# Modul_PCB.net
KiCad netlist of a schematic drawn in EAGLE
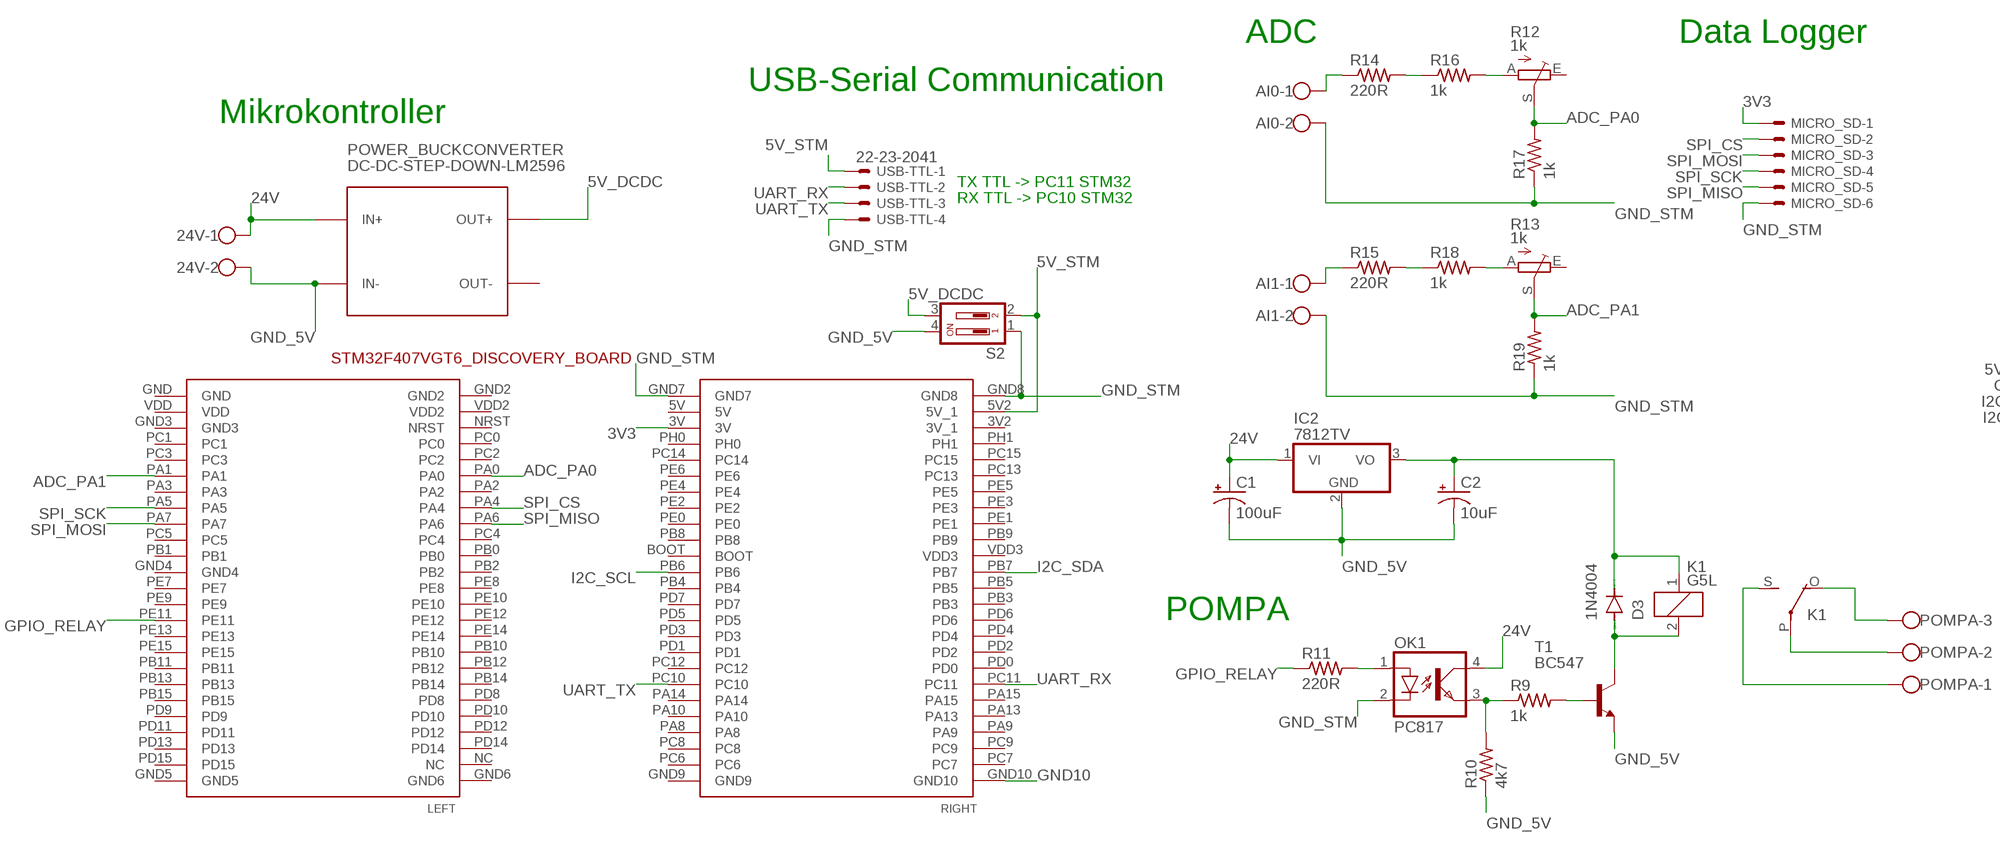
[diagram p0: schematic, sheet 1, part 1 of 2]
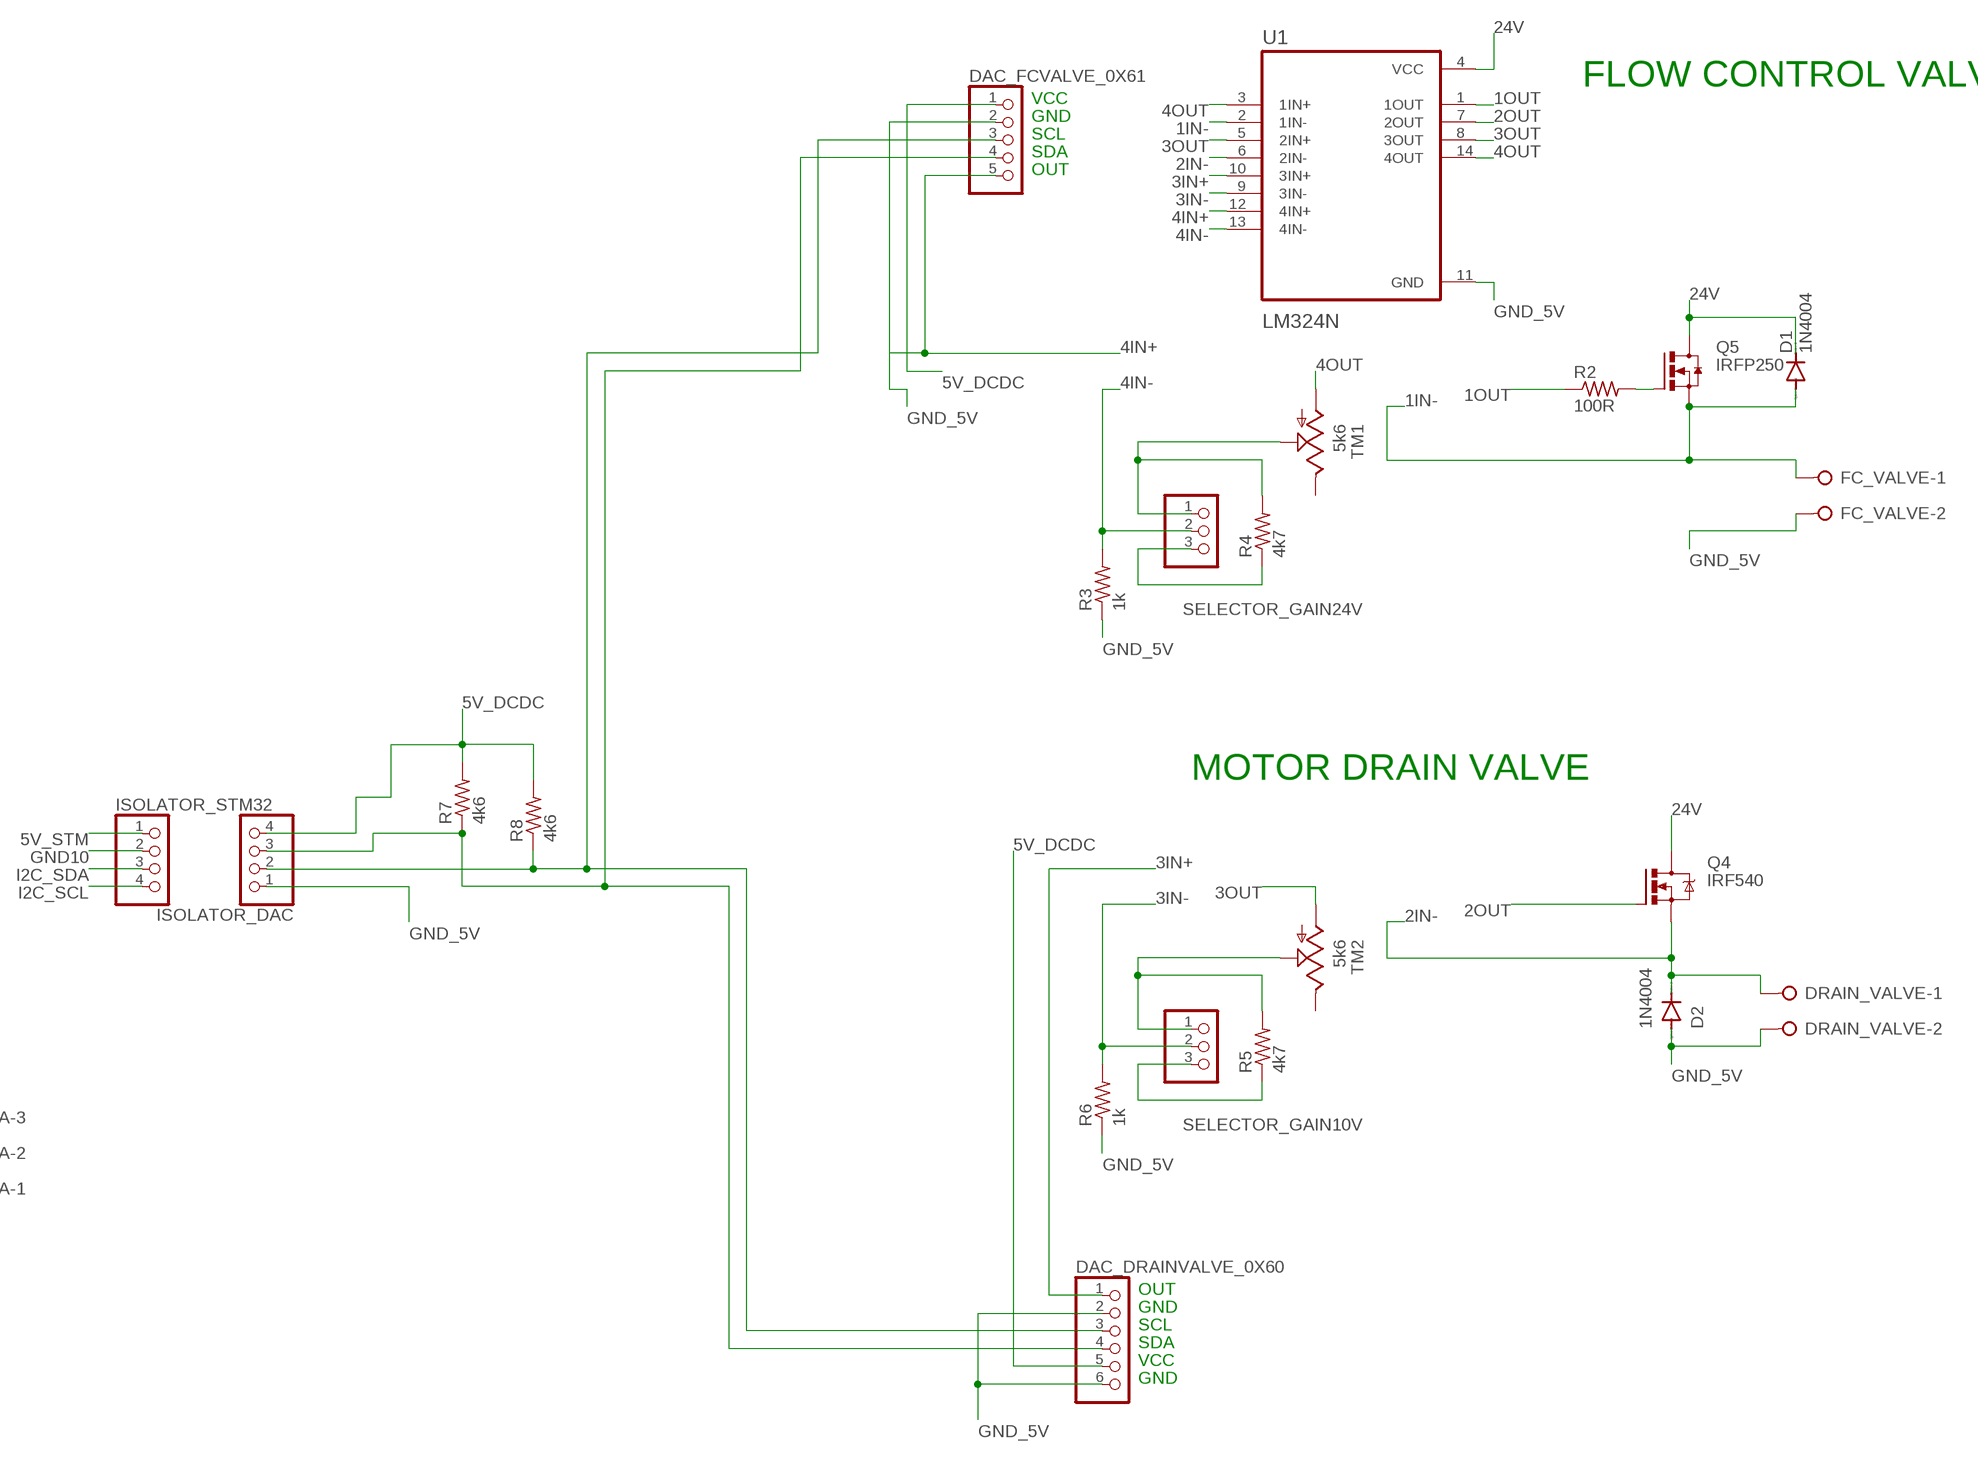
[diagram p1: schematic, sheet 1, part 2 of 2]

(export (version "E")
  (design (tool "Eeschema 10.0.6"))
  (components
    (comp (ref "24V")
      (value "W237-102")
      (footprint "eagle-import:W237-102")
      (fields (field (name "MPN") "237-102"))
      (libsource (lib "eagle-import") (part "W237-102"))
    )
    (comp (ref "AI0")
      (value "W237-102")
      (footprint "eagle-import:W237-102")
      (fields (field (name "MPN") "237-102"))
      (libsource (lib "eagle-import") (part "W237-102"))
    )
    (comp (ref "AI1")
      (value "W237-102")
      (footprint "eagle-import:W237-102")
      (fields (field (name "MPN") "237-102"))
      (libsource (lib "eagle-import") (part "W237-102"))
    )
    (comp (ref "C1")
      (value "100uF")
      (footprint "eagle-import:E2,5-6")
      (libsource (lib "eagle-import") (part "CPOL-USE2.5-6"))
    )
    (comp (ref "C2")
      (value "10uF")
      (footprint "eagle-import:E2,5-6")
      (libsource (lib "eagle-import") (part "CPOL-USE2.5-6"))
    )
    (comp (ref "D1")
      (value "1N4004")
      (footprint "eagle-import:DO41-10")
      (libsource (lib "eagle-import") (part "1N4004"))
    )
    (comp (ref "D2")
      (value "1N4004")
      (footprint "eagle-import:DO41-10")
      (libsource (lib "eagle-import") (part "1N4004"))
    )
    (comp (ref "D3")
      (value "1N4004")
      (footprint "eagle-import:DO41-10")
      (libsource (lib "eagle-import") (part "1N4004"))
    )
    (comp (ref "DAC_DRAINVALVE_0X60")
      (value "PINHD-1X6")
      (footprint "eagle-import:1X06")
      (libsource (lib "eagle-import") (part "PINHD-1X6"))
    )
    (comp (ref "DAC_FCVALVE_0X61")
      (value "PINHD-1X5")
      (footprint "eagle-import:1X05")
      (libsource (lib "eagle-import") (part "PINHD-1X5"))
    )
    (comp (ref "DRAIN_VALVE")
      (value "W237-02P")
      (footprint "eagle-import:W237-132")
      (libsource (lib "eagle-import") (part "W237-02P"))
    )
    (comp (ref "FC_VALVE")
      (value "W237-02P")
      (footprint "eagle-import:W237-132")
      (libsource (lib "eagle-import") (part "W237-02P"))
    )
    (comp (ref "IC2")
      (value "7812TV")
      (footprint "eagle-import:TO220V")
      (libsource (lib "eagle-import") (part "78TV12"))
    )
    (comp (ref "ISOLATOR_DAC")
      (value "PINHD-1X4")
      (footprint "eagle-import:1X04")
      (libsource (lib "eagle-import") (part "PINHD-1X4"))
    )
    (comp (ref "ISOLATOR_STM32")
      (value "PINHD-1X4")
      (footprint "eagle-import:1X04")
      (libsource (lib "eagle-import") (part "PINHD-1X4"))
    )
    (comp (ref "K1")
      (value "G5L")
      (footprint "eagle-import:G5LE")
      (libsource (lib "eagle-import") (part "G5L"))
    )
    (comp (ref "MICRO_SD")
      (value "22-23-2061")
      (footprint "eagle-import:22-23-2061")
      (fields (field (name "MF") "MOLEX"))
      (libsource (lib "eagle-import") (part "22-23-2061"))
    )
    (comp (ref "OK1")
      (value "PC817")
      (footprint "eagle-import:DIL04")
      (fields (field (name "MPN") "PC817X4J000F"))
      (libsource (lib "eagle-import") (part "PC817"))
    )
    (comp (ref "POMPA")
      (value "W237-103")
      (footprint "eagle-import:W237-103")
      (fields (field (name "MPN") "237-103"))
      (libsource (lib "eagle-import") (part "W237-103"))
    )
    (comp (ref "POWER_BUCKCONVERTER")
      (value "DC-DC-STEP-DOWN-LM2596")
      (footprint "eagle-import:DC-DC-STEP-DOWN-LM2596")
      (libsource (lib "eagle-import") (part "DC-DC-STEP-DOWN-LM2596"))
    )
    (comp (ref "Q4")
      (value "IRF540")
      (footprint "eagle-import:TO220BV")
      (libsource (lib "eagle-import") (part "IRF540"))
    )
    (comp (ref "Q5")
      (value "IRFP250")
      (footprint "eagle-import:TO-247AD-V")
      (libsource (lib "eagle-import") (part "IRFP250"))
    )
    (comp (ref "R2")
      (value "100R")
      (footprint "eagle-import:0207_10")
      (libsource (lib "eagle-import") (part "R-US_0207/10"))
    )
    (comp (ref "R3")
      (value "1k")
      (footprint "eagle-import:0207_10")
      (libsource (lib "eagle-import") (part "R-US_0207/10"))
    )
    (comp (ref "R4")
      (value "4k7")
      (footprint "eagle-import:0207_10")
      (libsource (lib "eagle-import") (part "R-US_0207/10"))
    )
    (comp (ref "R5")
      (value "4k7")
      (footprint "eagle-import:0207_10")
      (libsource (lib "eagle-import") (part "R-US_0207/10"))
    )
    (comp (ref "R6")
      (value "1k")
      (footprint "eagle-import:0207_10")
      (libsource (lib "eagle-import") (part "R-US_0207/10"))
    )
    (comp (ref "R7")
      (value "4k6")
      (footprint "eagle-import:0207_10")
      (libsource (lib "eagle-import") (part "R-US_0207/10"))
    )
    (comp (ref "R8")
      (value "4k6")
      (footprint "eagle-import:0207_10")
      (libsource (lib "eagle-import") (part "R-US_0207/10"))
    )
    (comp (ref "R9")
      (value "1k")
      (footprint "eagle-import:0207_10")
      (libsource (lib "eagle-import") (part "R-US_0207/10"))
    )
    (comp (ref "R10")
      (value "4k7")
      (footprint "eagle-import:0207_10")
      (libsource (lib "eagle-import") (part "R-US_0207/10"))
    )
    (comp (ref "R11")
      (value "220R")
      (footprint "eagle-import:0207_10")
      (libsource (lib "eagle-import") (part "R-US_0207/10"))
    )
    (comp (ref "R12")
      (value "1k")
      (footprint "eagle-import:RJ9W")
      (libsource (lib "eagle-import") (part "TRIM_EU-RJ9W"))
    )
    (comp (ref "R13")
      (value "1k")
      (footprint "eagle-import:RJ9W")
      (libsource (lib "eagle-import") (part "TRIM_EU-RJ9W"))
    )
    (comp (ref "R14")
      (value "220R")
      (footprint "eagle-import:0207_10")
      (libsource (lib "eagle-import") (part "R-US_0207/10"))
    )
    (comp (ref "R15")
      (value "220R")
      (footprint "eagle-import:0207_10")
      (libsource (lib "eagle-import") (part "R-US_0207/10"))
    )
    (comp (ref "R16")
      (value "1k")
      (footprint "eagle-import:0207_10")
      (libsource (lib "eagle-import") (part "R-US_0207/10"))
    )
    (comp (ref "R17")
      (value "1k")
      (footprint "eagle-import:0207_10")
      (libsource (lib "eagle-import") (part "R-US_0207/10"))
    )
    (comp (ref "R18")
      (value "1k")
      (footprint "eagle-import:0207_10")
      (libsource (lib "eagle-import") (part "R-US_0207/10"))
    )
    (comp (ref "R19")
      (value "1k")
      (footprint "eagle-import:0207_10")
      (libsource (lib "eagle-import") (part "R-US_0207/10"))
    )
    (comp (ref "S2")
      (value "DS02")
      (footprint "eagle-import:DS-02")
      (libsource (lib "eagle-import") (part "DS02"))
    )
    (comp (ref "SELECTOR_GAIN10V")
      (value "PINHD-1X3")
      (footprint "eagle-import:1X03")
      (libsource (lib "eagle-import") (part "PINHD-1X3"))
    )
    (comp (ref "SELECTOR_GAIN24V")
      (value "PINHD-1X3")
      (footprint "eagle-import:1X03")
      (libsource (lib "eagle-import") (part "PINHD-1X3"))
    )
    (comp (ref "STM32F407VGT6_DISCOVERY_BOARD")
      (value "STM32F4-DISCOVERY")
      (footprint "eagle-import:STM32F407VG")
      (libsource (lib "eagle-import") (part "STM32F4-DISCOVERY"))
    )
    (comp (ref "T1")
      (value "BC547")
      (footprint "eagle-import:TO92")
      (libsource (lib "eagle-import") (part "BC547"))
    )
    (comp (ref "TM1")
      (value "5k6")
      (footprint "eagle-import:6MM")
      (libsource (lib "eagle-import") (part "TRIM"))
    )
    (comp (ref "TM2")
      (value "5k6")
      (footprint "eagle-import:6MM")
      (libsource (lib "eagle-import") (part "TRIM"))
    )
    (comp (ref "U1")
      (value "LM324N")
      (footprint "eagle-import:DIP794W45P254L1969H508Q14")
      (fields (field (name "MF") "STMicroelectronics"))
      (libsource (lib "eagle-import") (part "LM324N"))
    )
    (comp (ref "USB-TTL")
      (value "22-23-2041")
      (footprint "eagle-import:22-23-2041")
      (fields (field (name "MF") "MOLEX"))
      (libsource (lib "eagle-import") (part "22-23-2041"))
    )
  )
  (nets
    (net (code "1") (name "/1IN-") (class "Default")
      (node (ref "D1") (pin "A") (pinfunction "A_A") (pintype "passive"))
      (node (ref "FC_VALVE") (pin "1") (pinfunction "KL_1") (pintype "passive"))
      (node (ref "Q5") (pin "S") (pinfunction "S_S") (pintype "passive"))
      (node (ref "U1") (pin "2") (pinfunction "1IN-_2") (pintype "input"))
    )
    (net (code "2") (name "/1OUT") (class "Default")
      (node (ref "R2") (pin "1") (pinfunction "1_1") (pintype "passive"))
      (node (ref "U1") (pin "1") (pinfunction "1OUT_1") (pintype "output"))
    )
    (net (code "3") (name "/2IN-") (class "Default")
      (node (ref "D2") (pin "C") (pinfunction "C_C") (pintype "passive"))
      (node (ref "DRAIN_VALVE") (pin "1") (pinfunction "KL_1") (pintype "passive"))
      (node (ref "Q4") (pin "S") (pinfunction "S_S") (pintype "passive"))
      (node (ref "U1") (pin "6") (pinfunction "2IN-_6") (pintype "input"))
    )
    (net (code "4") (name "/2OUT") (class "Default")
      (node (ref "Q4") (pin "G") (pinfunction "G_G") (pintype "passive"))
      (node (ref "U1") (pin "7") (pinfunction "2OUT_7") (pintype "output"))
    )
    (net (code "5") (name "/3IN+") (class "Default")
      (node (ref "DAC_DRAINVALVE_0X60") (pin "1") (pinfunction "1_1") (pintype "passive"))
      (node (ref "U1") (pin "10") (pinfunction "3IN+_10") (pintype "input"))
    )
    (net (code "6") (name "/3IN-") (class "Default")
      (node (ref "R6") (pin "2") (pinfunction "2_2") (pintype "passive"))
      (node (ref "SELECTOR_GAIN10V") (pin "2") (pinfunction "2_2") (pintype "passive"))
      (node (ref "U1") (pin "9") (pinfunction "3IN-_9") (pintype "input"))
    )
    (net (code "7") (name "/3OUT") (class "Default")
      (node (ref "TM2") (pin "A") (pinfunction "A_A") (pintype "passive"))
      (node (ref "U1") (pin "5") (pinfunction "2IN+_5") (pintype "input"))
      (node (ref "U1") (pin "8") (pinfunction "3OUT_8") (pintype "output"))
    )
    (net (code "8") (name "/3V3") (class "Default")
      (node (ref "MICRO_SD") (pin "1") (pinfunction "S_1") (pintype "passive"))
      (node (ref "STM32F407VGT6_DISCOVERY_BOARD") (pin "3V") (pinfunction "3V_3V") (pintype "bidirectional"))
    )
    (net (code "9") (name "/4IN+") (class "Default")
      (node (ref "DAC_FCVALVE_0X61") (pin "5") (pinfunction "5_5") (pintype "passive"))
      (node (ref "U1") (pin "12") (pinfunction "4IN+_12") (pintype "input"))
    )
    (net (code "10") (name "/4IN-") (class "Default")
      (node (ref "R3") (pin "2") (pinfunction "2_2") (pintype "passive"))
      (node (ref "SELECTOR_GAIN24V") (pin "2") (pinfunction "2_2") (pintype "passive"))
      (node (ref "U1") (pin "13") (pinfunction "4IN-_13") (pintype "input"))
    )
    (net (code "11") (name "/4OUT") (class "Default")
      (node (ref "TM1") (pin "A") (pinfunction "A_A") (pintype "passive"))
      (node (ref "U1") (pin "14") (pinfunction "4OUT_14") (pintype "output"))
      (node (ref "U1") (pin "3") (pinfunction "1IN+_3") (pintype "input"))
    )
    (net (code "12") (name "/5V_DCDC") (class "Default")
      (node (ref "DAC_DRAINVALVE_0X60") (pin "5") (pinfunction "5_5") (pintype "passive"))
      (node (ref "DAC_FCVALVE_0X61") (pin "1") (pinfunction "1_1") (pintype "passive"))
      (node (ref "ISOLATOR_DAC") (pin "4") (pinfunction "4_4") (pintype "passive"))
      (node (ref "POWER_BUCKCONVERTER") (pin "OUT+") (pinfunction "OUT+_OUT+") (pintype "bidirectional"))
      (node (ref "R7") (pin "2") (pinfunction "2_2") (pintype "passive"))
      (node (ref "R8") (pin "2") (pinfunction "2_2") (pintype "passive"))
      (node (ref "S2") (pin "3") (pinfunction "3_3") (pintype "passive"))
    )
    (net (code "13") (name "/5V_STM") (class "Default")
      (node (ref "ISOLATOR_STM32") (pin "1") (pinfunction "1_1") (pintype "passive"))
      (node (ref "S2") (pin "2") (pinfunction "2_2") (pintype "passive"))
      (node (ref "STM32F407VGT6_DISCOVERY_BOARD") (pin "5V2") (pinfunction "5V_1_5V2") (pintype "bidirectional"))
      (node (ref "USB-TTL") (pin "1") (pinfunction "S_1") (pintype "passive"))
    )
    (net (code "14") (name "/24V") (class "Default")
      (node (ref "24V") (pin "1") (pinfunction "KL_1") (pintype "passive"))
      (node (ref "C1") (pin "+") (pinfunction "+_+") (pintype "passive"))
      (node (ref "D1") (pin "C") (pinfunction "C_C") (pintype "passive"))
      (node (ref "IC2") (pin "1") (pinfunction "VI_1") (pintype "input"))
      (node (ref "OK1") (pin "4") (pinfunction "COL_4") (pintype "passive"))
      (node (ref "POWER_BUCKCONVERTER") (pin "IN+") (pinfunction "IN+_IN+") (pintype "bidirectional"))
      (node (ref "Q4") (pin "D") (pinfunction "D_D") (pintype "passive"))
      (node (ref "Q5") (pin "D") (pinfunction "D_D") (pintype "passive"))
      (node (ref "U1") (pin "4") (pinfunction "VCC_4") (pintype "power_in"))
    )
    (net (code "15") (name "/ADC_PA0") (class "Default")
      (node (ref "R12") (pin "S") (pinfunction "S_S") (pintype "passive"))
      (node (ref "R17") (pin "2") (pinfunction "2_2") (pintype "passive"))
      (node (ref "STM32F407VGT6_DISCOVERY_BOARD") (pin "PA0") (pinfunction "PA0_PA0") (pintype "bidirectional"))
    )
    (net (code "16") (name "/ADC_PA1") (class "Default")
      (node (ref "R13") (pin "S") (pinfunction "S_S") (pintype "passive"))
      (node (ref "R19") (pin "2") (pinfunction "2_2") (pintype "passive"))
      (node (ref "STM32F407VGT6_DISCOVERY_BOARD") (pin "PA1") (pinfunction "PA1_PA1") (pintype "bidirectional"))
    )
    (net (code "17") (name "/GND10") (class "Default")
      (node (ref "ISOLATOR_STM32") (pin "2") (pinfunction "2_2") (pintype "passive"))
      (node (ref "STM32F407VGT6_DISCOVERY_BOARD") (pin "GND10") (pinfunction "GND10_GND10") (pintype "bidirectional"))
    )
    (net (code "18") (name "/GND_5V") (class "Default")
      (node (ref "24V") (pin "2") (pinfunction "KL_2") (pintype "passive"))
      (node (ref "C1") (pin "-") (pinfunction "-_-") (pintype "passive"))
      (node (ref "C2") (pin "-") (pinfunction "-_-") (pintype "passive"))
      (node (ref "D2") (pin "A") (pinfunction "A_A") (pintype "passive"))
      (node (ref "DAC_DRAINVALVE_0X60") (pin "2") (pinfunction "2_2") (pintype "passive"))
      (node (ref "DAC_DRAINVALVE_0X60") (pin "6") (pinfunction "6_6") (pintype "passive"))
      (node (ref "DAC_FCVALVE_0X61") (pin "2") (pinfunction "2_2") (pintype "passive"))
      (node (ref "DRAIN_VALVE") (pin "2") (pinfunction "KL_2") (pintype "passive"))
      (node (ref "FC_VALVE") (pin "2") (pinfunction "KL_2") (pintype "passive"))
      (node (ref "IC2") (pin "2") (pinfunction "GND_2") (pintype "passive"))
      (node (ref "ISOLATOR_DAC") (pin "1") (pinfunction "1_1") (pintype "passive"))
      (node (ref "POWER_BUCKCONVERTER") (pin "IN-") (pinfunction "IN-_IN-") (pintype "bidirectional"))
      (node (ref "R10") (pin "1") (pinfunction "1_1") (pintype "passive"))
      (node (ref "R3") (pin "1") (pinfunction "1_1") (pintype "passive"))
      (node (ref "R6") (pin "1") (pinfunction "1_1") (pintype "passive"))
      (node (ref "S2") (pin "4") (pinfunction "4_4") (pintype "passive"))
      (node (ref "T1") (pin "1") (pinfunction "E_1") (pintype "passive"))
      (node (ref "U1") (pin "11") (pinfunction "GND_11") (pintype "power_in"))
    )
    (net (code "19") (name "/GND_STM") (class "Default")
      (node (ref "AI0") (pin "2") (pinfunction "KL_2") (pintype "passive"))
      (node (ref "AI1") (pin "2") (pinfunction "KL_2") (pintype "passive"))
      (node (ref "MICRO_SD") (pin "6") (pinfunction "S_6") (pintype "passive"))
      (node (ref "OK1") (pin "2") (pinfunction "C_2") (pintype "passive"))
      (node (ref "R17") (pin "1") (pinfunction "1_1") (pintype "passive"))
      (node (ref "R19") (pin "1") (pinfunction "1_1") (pintype "passive"))
      (node (ref "S2") (pin "1") (pinfunction "1_1") (pintype "passive"))
      (node (ref "STM32F407VGT6_DISCOVERY_BOARD") (pin "GND7") (pinfunction "GND7_GND7") (pintype "bidirectional"))
      (node (ref "STM32F407VGT6_DISCOVERY_BOARD") (pin "GND8") (pinfunction "GND8_GND8") (pintype "bidirectional"))
      (node (ref "USB-TTL") (pin "4") (pinfunction "S_4") (pintype "passive"))
    )
    (net (code "20") (name "/GPIO_RELAY") (class "Default")
      (node (ref "R11") (pin "1") (pinfunction "1_1") (pintype "passive"))
      (node (ref "STM32F407VGT6_DISCOVERY_BOARD") (pin "PE11") (pinfunction "PE11_PE11") (pintype "bidirectional"))
    )
    (net (code "21") (name "/I2C_SCL") (class "Default")
      (node (ref "ISOLATOR_STM32") (pin "4") (pinfunction "4_4") (pintype "passive"))
      (node (ref "STM32F407VGT6_DISCOVERY_BOARD") (pin "PB6") (pinfunction "PB6_PB6") (pintype "bidirectional"))
    )
    (net (code "22") (name "/I2C_SDA") (class "Default")
      (node (ref "ISOLATOR_STM32") (pin "3") (pinfunction "3_3") (pintype "passive"))
      (node (ref "STM32F407VGT6_DISCOVERY_BOARD") (pin "PB7") (pinfunction "PB7_PB7") (pintype "bidirectional"))
    )
    (net (code "23") (name "/SPI_CS") (class "Default")
      (node (ref "MICRO_SD") (pin "2") (pinfunction "S_2") (pintype "passive"))
      (node (ref "STM32F407VGT6_DISCOVERY_BOARD") (pin "PA4") (pinfunction "PA4_PA4") (pintype "bidirectional"))
    )
    (net (code "24") (name "/SPI_MISO") (class "Default")
      (node (ref "MICRO_SD") (pin "5") (pinfunction "S_5") (pintype "passive"))
      (node (ref "STM32F407VGT6_DISCOVERY_BOARD") (pin "PA6") (pinfunction "PA6_PA6") (pintype "bidirectional"))
    )
    (net (code "25") (name "/SPI_MOSI") (class "Default")
      (node (ref "MICRO_SD") (pin "3") (pinfunction "S_3") (pintype "passive"))
      (node (ref "STM32F407VGT6_DISCOVERY_BOARD") (pin "PA7") (pinfunction "PA7_PA7") (pintype "bidirectional"))
    )
    (net (code "26") (name "/SPI_SCK") (class "Default")
      (node (ref "MICRO_SD") (pin "4") (pinfunction "S_4") (pintype "passive"))
      (node (ref "STM32F407VGT6_DISCOVERY_BOARD") (pin "PA5") (pinfunction "PA5_PA5") (pintype "bidirectional"))
    )
    (net (code "27") (name "/UART_RX") (class "Default")
      (node (ref "STM32F407VGT6_DISCOVERY_BOARD") (pin "PC11") (pinfunction "PC11_PC11") (pintype "bidirectional"))
      (node (ref "USB-TTL") (pin "2") (pinfunction "S_2") (pintype "passive"))
    )
    (net (code "28") (name "/UART_TX") (class "Default")
      (node (ref "STM32F407VGT6_DISCOVERY_BOARD") (pin "PC10") (pinfunction "PC10_PC10") (pintype "bidirectional"))
      (node (ref "USB-TTL") (pin "3") (pinfunction "S_3") (pintype "passive"))
    )
    (net (code "29") (name "Net-(AI0A-KL)") (class "Default")
      (node (ref "AI0") (pin "1") (pinfunction "KL_1") (pintype "passive"))
      (node (ref "R14") (pin "1") (pinfunction "1_1") (pintype "passive"))
    )
    (net (code "30") (name "Net-(AI1A-KL)") (class "Default")
      (node (ref "AI1") (pin "1") (pinfunction "KL_1") (pintype "passive"))
      (node (ref "R15") (pin "1") (pinfunction "1_1") (pintype "passive"))
    )
    (net (code "31") (name "Net-(DAC_DRAINVALVE_0X60-Pad3)") (class "Default")
      (node (ref "DAC_DRAINVALVE_0X60") (pin "3") (pinfunction "3_3") (pintype "passive"))
      (node (ref "DAC_FCVALVE_0X61") (pin "3") (pinfunction "3_3") (pintype "passive"))
      (node (ref "ISOLATOR_DAC") (pin "2") (pinfunction "2_2") (pintype "passive"))
      (node (ref "R8") (pin "1") (pinfunction "1_1") (pintype "passive"))
    )
    (net (code "32") (name "Net-(DAC_DRAINVALVE_0X60-Pad4)") (class "Default")
      (node (ref "DAC_DRAINVALVE_0X60") (pin "4") (pinfunction "4_4") (pintype "passive"))
      (node (ref "DAC_FCVALVE_0X61") (pin "4") (pinfunction "4_4") (pintype "passive"))
      (node (ref "ISOLATOR_DAC") (pin "3") (pinfunction "3_3") (pintype "passive"))
      (node (ref "R7") (pin "1") (pinfunction "1_1") (pintype "passive"))
    )
    (net (code "33") (name "Net-(IC2-VO)") (class "Default")
      (node (ref "C2") (pin "+") (pinfunction "+_+") (pintype "passive"))
      (node (ref "D3") (pin "C") (pinfunction "C_C") (pintype "passive"))
      (node (ref "IC2") (pin "3") (pinfunction "VO_3") (pintype "passive"))
      (node (ref "K1") (pin "1") (pinfunction "1_1") (pintype "passive"))
    )
    (net (code "34") (name "Net-(OK1-A)") (class "Default")
      (node (ref "OK1") (pin "1") (pinfunction "A_1") (pintype "passive"))
      (node (ref "R11") (pin "2") (pinfunction "2_2") (pintype "passive"))
    )
    (net (code "35") (name "Net-(OK1-EMIT)") (class "Default")
      (node (ref "OK1") (pin "3") (pinfunction "EMIT_3") (pintype "passive"))
      (node (ref "R10") (pin "2") (pinfunction "2_2") (pintype "passive"))
      (node (ref "R9") (pin "1") (pinfunction "1_1") (pintype "passive"))
    )
    (net (code "36") (name "Net-(POMPAA-KL)") (class "Default")
      (node (ref "K1") (pin "S") (pinfunction "S_S") (pintype "passive"))
      (node (ref "POMPA") (pin "1") (pinfunction "KL_1") (pintype "passive"))
    )
    (net (code "37") (name "Net-(POMPAB-KL)") (class "Default")
      (node (ref "K1") (pin "P") (pinfunction "P_P") (pintype "passive"))
      (node (ref "POMPA") (pin "2") (pinfunction "KL_2") (pintype "passive"))
    )
    (net (code "38") (name "Net-(POMPAC-KL)") (class "Default")
      (node (ref "K1") (pin "O") (pinfunction "O_O") (pintype "passive"))
      (node (ref "POMPA") (pin "3") (pinfunction "KL_3") (pintype "passive"))
    )
    (net (code "39") (name "Net-(Q5-PadG)") (class "Default")
      (node (ref "Q5") (pin "G") (pinfunction "G_G") (pintype "passive"))
      (node (ref "R2") (pin "2") (pinfunction "2_2") (pintype "passive"))
    )
    (net (code "40") (name "Net-(R4-Pad1)") (class "Default")
      (node (ref "R4") (pin "1") (pinfunction "1_1") (pintype "passive"))
      (node (ref "SELECTOR_GAIN24V") (pin "3") (pinfunction "3_3") (pintype "passive"))
    )
    (net (code "41") (name "Net-(R4-Pad2)") (class "Default")
      (node (ref "R4") (pin "2") (pinfunction "2_2") (pintype "passive"))
      (node (ref "SELECTOR_GAIN24V") (pin "1") (pinfunction "1_1") (pintype "passive"))
      (node (ref "TM1") (pin "S") (pinfunction "S_S") (pintype "passive"))
    )
    (net (code "42") (name "Net-(R5-Pad1)") (class "Default")
      (node (ref "R5") (pin "1") (pinfunction "1_1") (pintype "passive"))
      (node (ref "SELECTOR_GAIN10V") (pin "3") (pinfunction "3_3") (pintype "passive"))
    )
    (net (code "43") (name "Net-(R5-Pad2)") (class "Default")
      (node (ref "R5") (pin "2") (pinfunction "2_2") (pintype "passive"))
      (node (ref "SELECTOR_GAIN10V") (pin "1") (pinfunction "1_1") (pintype "passive"))
      (node (ref "TM2") (pin "S") (pinfunction "S_S") (pintype "passive"))
    )
    (net (code "44") (name "Net-(R12-PadA)") (class "Default")
      (node (ref "R12") (pin "A") (pinfunction "A_A") (pintype "passive"))
      (node (ref "R16") (pin "2") (pinfunction "2_2") (pintype "passive"))
    )
    (net (code "45") (name "Net-(R13-PadA)") (class "Default")
      (node (ref "R13") (pin "A") (pinfunction "A_A") (pintype "passive"))
      (node (ref "R18") (pin "2") (pinfunction "2_2") (pintype "passive"))
    )
    (net (code "46") (name "Net-(R14-Pad2)") (class "Default")
      (node (ref "R14") (pin "2") (pinfunction "2_2") (pintype "passive"))
      (node (ref "R16") (pin "1") (pinfunction "1_1") (pintype "passive"))
    )
    (net (code "47") (name "Net-(R15-Pad2)") (class "Default")
      (node (ref "R15") (pin "2") (pinfunction "2_2") (pintype "passive"))
      (node (ref "R18") (pin "1") (pinfunction "1_1") (pintype "passive"))
    )
    (net (code "48") (name "Net-(T1-B)") (class "Default")
      (node (ref "R9") (pin "2") (pinfunction "2_2") (pintype "passive"))
      (node (ref "T1") (pin "2") (pinfunction "B_2") (pintype "passive"))
    )
    (net (code "49") (name "Net-(T1-C)") (class "Default")
      (node (ref "D3") (pin "A") (pinfunction "A_A") (pintype "passive"))
      (node (ref "K1") (pin "2") (pinfunction "2_2") (pintype "passive"))
      (node (ref "T1") (pin "3") (pinfunction "C_3") (pintype "passive"))
    )
    (net (code "50") (name "unconnected-(POWER_BUCKCONVERTER-PadOUT-)") (class "Default")
      (node (ref "POWER_BUCKCONVERTER") (pin "OUT-") (pinfunction "OUT-_OUT-") (pintype "bidirectional"))
    )
    (net (code "51") (name "unconnected-(R12-PadE)") (class "Default")
      (node (ref "R12") (pin "E") (pinfunction "E_E") (pintype "passive"))
    )
    (net (code "52") (name "unconnected-(R13-PadE)") (class "Default")
      (node (ref "R13") (pin "E") (pinfunction "E_E") (pintype "passive"))
    )
    (net (code "53") (name "unconnected-(STM32F407VGT6_DISCOVERY_BOARD-3V_1-Pad3V2)") (class "Default")
      (node (ref "STM32F407VGT6_DISCOVERY_BOARD") (pin "3V2") (pinfunction "3V_1_3V2") (pintype "bidirectional"))
    )
    (net (code "54") (name "unconnected-(STM32F407VGT6_DISCOVERY_BOARD-Pad5V)") (class "Default")
      (node (ref "STM32F407VGT6_DISCOVERY_BOARD") (pin "5V") (pinfunction "5V_5V") (pintype "bidirectional"))
    )
    (net (code "55") (name "unconnected-(STM32F407VGT6_DISCOVERY_BOARD-PadBOOT)") (class "Default")
      (node (ref "STM32F407VGT6_DISCOVERY_BOARD") (pin "BOOT") (pinfunction "BOOT_BOOT") (pintype "bidirectional"))
    )
    (net (code "56") (name "unconnected-(STM32F407VGT6_DISCOVERY_BOARD-PadGND)") (class "Default")
      (node (ref "STM32F407VGT6_DISCOVERY_BOARD") (pin "GND") (pinfunction "GND_GND") (pintype "bidirectional"))
    )
    (net (code "57") (name "unconnected-(STM32F407VGT6_DISCOVERY_BOARD-PadGND2)") (class "Default")
      (node (ref "STM32F407VGT6_DISCOVERY_BOARD") (pin "GND2") (pinfunction "GND2_GND2") (pintype "bidirectional"))
    )
    (net (code "58") (name "unconnected-(STM32F407VGT6_DISCOVERY_BOARD-PadGND3)") (class "Default")
      (node (ref "STM32F407VGT6_DISCOVERY_BOARD") (pin "GND3") (pinfunction "GND3_GND3") (pintype "bidirectional"))
    )
    (net (code "59") (name "unconnected-(STM32F407VGT6_DISCOVERY_BOARD-PadGND4)") (class "Default")
      (node (ref "STM32F407VGT6_DISCOVERY_BOARD") (pin "GND4") (pinfunction "GND4_GND4") (pintype "bidirectional"))
    )
    (net (code "60") (name "unconnected-(STM32F407VGT6_DISCOVERY_BOARD-PadGND5)") (class "Default")
      (node (ref "STM32F407VGT6_DISCOVERY_BOARD") (pin "GND5") (pinfunction "GND5_GND5") (pintype "bidirectional"))
    )
    (net (code "61") (name "unconnected-(STM32F407VGT6_DISCOVERY_BOARD-PadGND6)") (class "Default")
      (node (ref "STM32F407VGT6_DISCOVERY_BOARD") (pin "GND6") (pinfunction "GND6_GND6") (pintype "bidirectional"))
    )
    (net (code "62") (name "unconnected-(STM32F407VGT6_DISCOVERY_BOARD-PadGND9)") (class "Default")
      (node (ref "STM32F407VGT6_DISCOVERY_BOARD") (pin "GND9") (pinfunction "GND9_GND9") (pintype "bidirectional"))
    )
    (net (code "63") (name "unconnected-(STM32F407VGT6_DISCOVERY_BOARD-PadNC)") (class "Default")
      (node (ref "STM32F407VGT6_DISCOVERY_BOARD") (pin "NC") (pinfunction "NC_NC") (pintype "bidirectional"))
    )
    (net (code "64") (name "unconnected-(STM32F407VGT6_DISCOVERY_BOARD-PadNRST)") (class "Default")
      (node (ref "STM32F407VGT6_DISCOVERY_BOARD") (pin "NRST") (pinfunction "NRST_NRST") (pintype "bidirectional"))
    )
    (net (code "65") (name "unconnected-(STM32F407VGT6_DISCOVERY_BOARD-PadPA2)") (class "Default")
      (node (ref "STM32F407VGT6_DISCOVERY_BOARD") (pin "PA2") (pinfunction "PA2_PA2") (pintype "bidirectional"))
    )
    (net (code "66") (name "unconnected-(STM32F407VGT6_DISCOVERY_BOARD-PadPA3)") (class "Default")
      (node (ref "STM32F407VGT6_DISCOVERY_BOARD") (pin "PA3") (pinfunction "PA3_PA3") (pintype "bidirectional"))
    )
    (net (code "67") (name "unconnected-(STM32F407VGT6_DISCOVERY_BOARD-PadPA8)") (class "Default")
      (node (ref "STM32F407VGT6_DISCOVERY_BOARD") (pin "PA8") (pinfunction "PA8_PA8") (pintype "bidirectional"))
    )
    (net (code "68") (name "unconnected-(STM32F407VGT6_DISCOVERY_BOARD-PadPA9)") (class "Default")
      (node (ref "STM32F407VGT6_DISCOVERY_BOARD") (pin "PA9") (pinfunction "PA9_PA9") (pintype "bidirectional"))
    )
    (net (code "69") (name "unconnected-(STM32F407VGT6_DISCOVERY_BOARD-PadPA10)") (class "Default")
      (node (ref "STM32F407VGT6_DISCOVERY_BOARD") (pin "PA10") (pinfunction "PA10_PA10") (pintype "bidirectional"))
    )
    (net (code "70") (name "unconnected-(STM32F407VGT6_DISCOVERY_BOARD-PadPA13)") (class "Default")
      (node (ref "STM32F407VGT6_DISCOVERY_BOARD") (pin "PA13") (pinfunction "PA13_PA13") (pintype "bidirectional"))
    )
    (net (code "71") (name "unconnected-(STM32F407VGT6_DISCOVERY_BOARD-PadPA14)") (class "Default")
      (node (ref "STM32F407VGT6_DISCOVERY_BOARD") (pin "PA14") (pinfunction "PA14_PA14") (pintype "bidirectional"))
    )
    (net (code "72") (name "unconnected-(STM32F407VGT6_DISCOVERY_BOARD-PadPA15)") (class "Default")
      (node (ref "STM32F407VGT6_DISCOVERY_BOARD") (pin "PA15") (pinfunction "PA15_PA15") (pintype "bidirectional"))
    )
    (net (code "73") (name "unconnected-(STM32F407VGT6_DISCOVERY_BOARD-PadPB0)") (class "Default")
      (node (ref "STM32F407VGT6_DISCOVERY_BOARD") (pin "PB0") (pinfunction "PB0_PB0") (pintype "bidirectional"))
    )
    (net (code "74") (name "unconnected-(STM32F407VGT6_DISCOVERY_BOARD-PadPB1)") (class "Default")
      (node (ref "STM32F407VGT6_DISCOVERY_BOARD") (pin "PB1") (pinfunction "PB1_PB1") (pintype "bidirectional"))
    )
    (net (code "75") (name "unconnected-(STM32F407VGT6_DISCOVERY_BOARD-PadPB2)") (class "Default")
      (node (ref "STM32F407VGT6_DISCOVERY_BOARD") (pin "PB2") (pinfunction "PB2_PB2") (pintype "bidirectional"))
    )
    (net (code "76") (name "unconnected-(STM32F407VGT6_DISCOVERY_BOARD-PadPB3)") (class "Default")
      (node (ref "STM32F407VGT6_DISCOVERY_BOARD") (pin "PB3") (pinfunction "PB3_PB3") (pintype "bidirectional"))
    )
    (net (code "77") (name "unconnected-(STM32F407VGT6_DISCOVERY_BOARD-PadPB4)") (class "Default")
      (node (ref "STM32F407VGT6_DISCOVERY_BOARD") (pin "PB4") (pinfunction "PB4_PB4") (pintype "bidirectional"))
    )
    (net (code "78") (name "unconnected-(STM32F407VGT6_DISCOVERY_BOARD-PadPB5)") (class "Default")
      (node (ref "STM32F407VGT6_DISCOVERY_BOARD") (pin "PB5") (pinfunction "PB5_PB5") (pintype "bidirectional"))
    )
    (net (code "79") (name "unconnected-(STM32F407VGT6_DISCOVERY_BOARD-PadPB8)") (class "Default")
      (node (ref "STM32F407VGT6_DISCOVERY_BOARD") (pin "PB8") (pinfunction "PB8_PB8") (pintype "bidirectional"))
    )
    (net (code "80") (name "unconnected-(STM32F407VGT6_DISCOVERY_BOARD-PadPB9)") (class "Default")
      (node (ref "STM32F407VGT6_DISCOVERY_BOARD") (pin "PB9") (pinfunction "PB9_PB9") (pintype "bidirectional"))
    )
    (net (code "81") (name "unconnected-(STM32F407VGT6_DISCOVERY_BOARD-PadPB10)") (class "Default")
      (node (ref "STM32F407VGT6_DISCOVERY_BOARD") (pin "PB10") (pinfunction "PB10_PB10") (pintype "bidirectional"))
    )
    (net (code "82") (name "unconnected-(STM32F407VGT6_DISCOVERY_BOARD-PadPB11)") (class "Default")
      (node (ref "STM32F407VGT6_DISCOVERY_BOARD") (pin "PB11") (pinfunction "PB11_PB11") (pintype "bidirectional"))
    )
    (net (code "83") (name "unconnected-(STM32F407VGT6_DISCOVERY_BOARD-PadPB12)") (class "Default")
      (node (ref "STM32F407VGT6_DISCOVERY_BOARD") (pin "PB12") (pinfunction "PB12_PB12") (pintype "bidirectional"))
    )
    (net (code "84") (name "unconnected-(STM32F407VGT6_DISCOVERY_BOARD-PadPB13)") (class "Default")
      (node (ref "STM32F407VGT6_DISCOVERY_BOARD") (pin "PB13") (pinfunction "PB13_PB13") (pintype "bidirectional"))
    )
    (net (code "85") (name "unconnected-(STM32F407VGT6_DISCOVERY_BOARD-PadPB14)") (class "Default")
      (node (ref "STM32F407VGT6_DISCOVERY_BOARD") (pin "PB14") (pinfunction "PB14_PB14") (pintype "bidirectional"))
    )
    (net (code "86") (name "unconnected-(STM32F407VGT6_DISCOVERY_BOARD-PadPB15)") (class "Default")
      (node (ref "STM32F407VGT6_DISCOVERY_BOARD") (pin "PB15") (pinfunction "PB15_PB15") (pintype "bidirectional"))
    )
    (net (code "87") (name "unconnected-(STM32F407VGT6_DISCOVERY_BOARD-PadPC0)") (class "Default")
      (node (ref "STM32F407VGT6_DISCOVERY_BOARD") (pin "PC0") (pinfunction "PC0_PC0") (pintype "bidirectional"))
    )
    (net (code "88") (name "unconnected-(STM32F407VGT6_DISCOVERY_BOARD-PadPC1)") (class "Default")
      (node (ref "STM32F407VGT6_DISCOVERY_BOARD") (pin "PC1") (pinfunction "PC1_PC1") (pintype "bidirectional"))
    )
    (net (code "89") (name "unconnected-(STM32F407VGT6_DISCOVERY_BOARD-PadPC2)") (class "Default")
      (node (ref "STM32F407VGT6_DISCOVERY_BOARD") (pin "PC2") (pinfunction "PC2_PC2") (pintype "bidirectional"))
    )
    (net (code "90") (name "unconnected-(STM32F407VGT6_DISCOVERY_BOARD-PadPC3)") (class "Default")
      (node (ref "STM32F407VGT6_DISCOVERY_BOARD") (pin "PC3") (pinfunction "PC3_PC3") (pintype "bidirectional"))
    )
    (net (code "91") (name "unconnected-(STM32F407VGT6_DISCOVERY_BOARD-PadPC4)") (class "Default")
      (node (ref "STM32F407VGT6_DISCOVERY_BOARD") (pin "PC4") (pinfunction "PC4_PC4") (pintype "bidirectional"))
    )
    (net (code "92") (name "unconnected-(STM32F407VGT6_DISCOVERY_BOARD-PadPC5)") (class "Default")
      (node (ref "STM32F407VGT6_DISCOVERY_BOARD") (pin "PC5") (pinfunction "PC5_PC5") (pintype "bidirectional"))
    )
    (net (code "93") (name "unconnected-(STM32F407VGT6_DISCOVERY_BOARD-PadPC6)") (class "Default")
      (node (ref "STM32F407VGT6_DISCOVERY_BOARD") (pin "PC6") (pinfunction "PC6_PC6") (pintype "bidirectional"))
    )
    (net (code "94") (name "unconnected-(STM32F407VGT6_DISCOVERY_BOARD-PadPC7)") (class "Default")
      (node (ref "STM32F407VGT6_DISCOVERY_BOARD") (pin "PC7") (pinfunction "PC7_PC7") (pintype "bidirectional"))
    )
    (net (code "95") (name "unconnected-(STM32F407VGT6_DISCOVERY_BOARD-PadPC8)") (class "Default")
      (node (ref "STM32F407VGT6_DISCOVERY_BOARD") (pin "PC8") (pinfunction "PC8_PC8") (pintype "bidirectional"))
    )
    (net (code "96") (name "unconnected-(STM32F407VGT6_DISCOVERY_BOARD-PadPC9)") (class "Default")
      (node (ref "STM32F407VGT6_DISCOVERY_BOARD") (pin "PC9") (pinfunction "PC9_PC9") (pintype "bidirectional"))
    )
    (net (code "97") (name "unconnected-(STM32F407VGT6_DISCOVERY_BOARD-PadPC12)") (class "Default")
      (node (ref "STM32F407VGT6_DISCOVERY_BOARD") (pin "PC12") (pinfunction "PC12_PC12") (pintype "bidirectional"))
    )
    (net (code "98") (name "unconnected-(STM32F407VGT6_DISCOVERY_BOARD-PadPC13)") (class "Default")
      (node (ref "STM32F407VGT6_DISCOVERY_BOARD") (pin "PC13") (pinfunction "PC13_PC13") (pintype "bidirectional"))
    )
    (net (code "99") (name "unconnected-(STM32F407VGT6_DISCOVERY_BOARD-PadPC14)") (class "Default")
      (node (ref "STM32F407VGT6_DISCOVERY_BOARD") (pin "PC14") (pinfunction "PC14_PC14") (pintype "bidirectional"))
    )
    (net (code "100") (name "unconnected-(STM32F407VGT6_DISCOVERY_BOARD-PadPC15)") (class "Default")
      (node (ref "STM32F407VGT6_DISCOVERY_BOARD") (pin "PC15") (pinfunction "PC15_PC15") (pintype "bidirectional"))
    )
    (net (code "101") (name "unconnected-(STM32F407VGT6_DISCOVERY_BOARD-PadPD0)") (class "Default")
      (node (ref "STM32F407VGT6_DISCOVERY_BOARD") (pin "PD0") (pinfunction "PD0_PD0") (pintype "bidirectional"))
    )
    (net (code "102") (name "unconnected-(STM32F407VGT6_DISCOVERY_BOARD-PadPD1)") (class "Default")
      (node (ref "STM32F407VGT6_DISCOVERY_BOARD") (pin "PD1") (pinfunction "PD1_PD1") (pintype "bidirectional"))
    )
    (net (code "103") (name "unconnected-(STM32F407VGT6_DISCOVERY_BOARD-PadPD2)") (class "Default")
      (node (ref "STM32F407VGT6_DISCOVERY_BOARD") (pin "PD2") (pinfunction "PD2_PD2") (pintype "bidirectional"))
    )
    (net (code "104") (name "unconnected-(STM32F407VGT6_DISCOVERY_BOARD-PadPD3)") (class "Default")
      (node (ref "STM32F407VGT6_DISCOVERY_BOARD") (pin "PD3") (pinfunction "PD3_PD3") (pintype "bidirectional"))
    )
    (net (code "105") (name "unconnected-(STM32F407VGT6_DISCOVERY_BOARD-PadPD4)") (class "Default")
      (node (ref "STM32F407VGT6_DISCOVERY_BOARD") (pin "PD4") (pinfunction "PD4_PD4") (pintype "bidirectional"))
    )
    (net (code "106") (name "unconnected-(STM32F407VGT6_DISCOVERY_BOARD-PadPD5)") (class "Default")
      (node (ref "STM32F407VGT6_DISCOVERY_BOARD") (pin "PD5") (pinfunction "PD5_PD5") (pintype "bidirectional"))
    )
    (net (code "107") (name "unconnected-(STM32F407VGT6_DISCOVERY_BOARD-PadPD6)") (class "Default")
      (node (ref "STM32F407VGT6_DISCOVERY_BOARD") (pin "PD6") (pinfunction "PD6_PD6") (pintype "bidirectional"))
    )
    (net (code "108") (name "unconnected-(STM32F407VGT6_DISCOVERY_BOARD-PadPD7)") (class "Default")
      (node (ref "STM32F407VGT6_DISCOVERY_BOARD") (pin "PD7") (pinfunction "PD7_PD7") (pintype "bidirectional"))
    )
    (net (code "109") (name "unconnected-(STM32F407VGT6_DISCOVERY_BOARD-PadPD8)") (class "Default")
      (node (ref "STM32F407VGT6_DISCOVERY_BOARD") (pin "PD8") (pinfunction "PD8_PD8") (pintype "bidirectional"))
    )
    (net (code "110") (name "unconnected-(STM32F407VGT6_DISCOVERY_BOARD-PadPD9)") (class "Default")
      (node (ref "STM32F407VGT6_DISCOVERY_BOARD") (pin "PD9") (pinfunction "PD9_PD9") (pintype "bidirectional"))
    )
    (net (code "111") (name "unconnected-(STM32F407VGT6_DISCOVERY_BOARD-PadPD10)") (class "Default")
      (node (ref "STM32F407VGT6_DISCOVERY_BOARD") (pin "PD10") (pinfunction "PD10_PD10") (pintype "bidirectional"))
    )
    (net (code "112") (name "unconnected-(STM32F407VGT6_DISCOVERY_BOARD-PadPD11)") (class "Default")
      (node (ref "STM32F407VGT6_DISCOVERY_BOARD") (pin "PD11") (pinfunction "PD11_PD11") (pintype "bidirectional"))
    )
    (net (code "113") (name "unconnected-(STM32F407VGT6_DISCOVERY_BOARD-PadPD12)") (class "Default")
      (node (ref "STM32F407VGT6_DISCOVERY_BOARD") (pin "PD12") (pinfunction "PD12_PD12") (pintype "bidirectional"))
    )
    (net (code "114") (name "unconnected-(STM32F407VGT6_DISCOVERY_BOARD-PadPD13)") (class "Default")
      (node (ref "STM32F407VGT6_DISCOVERY_BOARD") (pin "PD13") (pinfunction "PD13_PD13") (pintype "bidirectional"))
    )
    (net (code "115") (name "unconnected-(STM32F407VGT6_DISCOVERY_BOARD-PadPD14)") (class "Default")
      (node (ref "STM32F407VGT6_DISCOVERY_BOARD") (pin "PD14") (pinfunction "PD14_PD14") (pintype "bidirectional"))
    )
    (net (code "116") (name "unconnected-(STM32F407VGT6_DISCOVERY_BOARD-PadPD15)") (class "Default")
      (node (ref "STM32F407VGT6_DISCOVERY_BOARD") (pin "PD15") (pinfunction "PD15_PD15") (pintype "bidirectional"))
    )
    (net (code "117") (name "unconnected-(STM32F407VGT6_DISCOVERY_BOARD-PadPE0)") (class "Default")
      (node (ref "STM32F407VGT6_DISCOVERY_BOARD") (pin "PE0") (pinfunction "PE0_PE0") (pintype "bidirectional"))
    )
    (net (code "118") (name "unconnected-(STM32F407VGT6_DISCOVERY_BOARD-PadPE1)") (class "Default")
      (node (ref "STM32F407VGT6_DISCOVERY_BOARD") (pin "PE1") (pinfunction "PE1_PE1") (pintype "bidirectional"))
    )
    (net (code "119") (name "unconnected-(STM32F407VGT6_DISCOVERY_BOARD-PadPE2)") (class "Default")
      (node (ref "STM32F407VGT6_DISCOVERY_BOARD") (pin "PE2") (pinfunction "PE2_PE2") (pintype "bidirectional"))
    )
    (net (code "120") (name "unconnected-(STM32F407VGT6_DISCOVERY_BOARD-PadPE3)") (class "Default")
      (node (ref "STM32F407VGT6_DISCOVERY_BOARD") (pin "PE3") (pinfunction "PE3_PE3") (pintype "bidirectional"))
    )
    (net (code "121") (name "unconnected-(STM32F407VGT6_DISCOVERY_BOARD-PadPE4)") (class "Default")
      (node (ref "STM32F407VGT6_DISCOVERY_BOARD") (pin "PE4") (pinfunction "PE4_PE4") (pintype "bidirectional"))
    )
    (net (code "122") (name "unconnected-(STM32F407VGT6_DISCOVERY_BOARD-PadPE5)") (class "Default")
      (node (ref "STM32F407VGT6_DISCOVERY_BOARD") (pin "PE5") (pinfunction "PE5_PE5") (pintype "bidirectional"))
    )
    (net (code "123") (name "unconnected-(STM32F407VGT6_DISCOVERY_BOARD-PadPE6)") (class "Default")
      (node (ref "STM32F407VGT6_DISCOVERY_BOARD") (pin "PE6") (pinfunction "PE6_PE6") (pintype "bidirectional"))
    )
    (net (code "124") (name "unconnected-(STM32F407VGT6_DISCOVERY_BOARD-PadPE7)") (class "Default")
      (node (ref "STM32F407VGT6_DISCOVERY_BOARD") (pin "PE7") (pinfunction "PE7_PE7") (pintype "bidirectional"))
    )
    (net (code "125") (name "unconnected-(STM32F407VGT6_DISCOVERY_BOARD-PadPE8)") (class "Default")
      (node (ref "STM32F407VGT6_DISCOVERY_BOARD") (pin "PE8") (pinfunction "PE8_PE8") (pintype "bidirectional"))
    )
    (net (code "126") (name "unconnected-(STM32F407VGT6_DISCOVERY_BOARD-PadPE9)") (class "Default")
      (node (ref "STM32F407VGT6_DISCOVERY_BOARD") (pin "PE9") (pinfunction "PE9_PE9") (pintype "bidirectional"))
    )
    (net (code "127") (name "unconnected-(STM32F407VGT6_DISCOVERY_BOARD-PadPE10)") (class "Default")
      (node (ref "STM32F407VGT6_DISCOVERY_BOARD") (pin "PE10") (pinfunction "PE10_PE10") (pintype "bidirectional"))
    )
    (net (code "128") (name "unconnected-(STM32F407VGT6_DISCOVERY_BOARD-PadPE12)") (class "Default")
      (node (ref "STM32F407VGT6_DISCOVERY_BOARD") (pin "PE12") (pinfunction "PE12_PE12") (pintype "bidirectional"))
    )
    (net (code "129") (name "unconnected-(STM32F407VGT6_DISCOVERY_BOARD-PadPE13)") (class "Default")
      (node (ref "STM32F407VGT6_DISCOVERY_BOARD") (pin "PE13") (pinfunction "PE13_PE13") (pintype "bidirectional"))
    )
    (net (code "130") (name "unconnected-(STM32F407VGT6_DISCOVERY_BOARD-PadPE14)") (class "Default")
      (node (ref "STM32F407VGT6_DISCOVERY_BOARD") (pin "PE14") (pinfunction "PE14_PE14") (pintype "bidirectional"))
    )
    (net (code "131") (name "unconnected-(STM32F407VGT6_DISCOVERY_BOARD-PadPE15)") (class "Default")
      (node (ref "STM32F407VGT6_DISCOVERY_BOARD") (pin "PE15") (pinfunction "PE15_PE15") (pintype "bidirectional"))
    )
    (net (code "132") (name "unconnected-(STM32F407VGT6_DISCOVERY_BOARD-PadPH0)") (class "Default")
      (node (ref "STM32F407VGT6_DISCOVERY_BOARD") (pin "PH0") (pinfunction "PH0_PH0") (pintype "bidirectional"))
    )
    (net (code "133") (name "unconnected-(STM32F407VGT6_DISCOVERY_BOARD-PadPH1)") (class "Default")
      (node (ref "STM32F407VGT6_DISCOVERY_BOARD") (pin "PH1") (pinfunction "PH1_PH1") (pintype "bidirectional"))
    )
    (net (code "134") (name "unconnected-(STM32F407VGT6_DISCOVERY_BOARD-PadVDD)") (class "Default")
      (node (ref "STM32F407VGT6_DISCOVERY_BOARD") (pin "VDD") (pinfunction "VDD_VDD") (pintype "bidirectional"))
    )
    (net (code "135") (name "unconnected-(STM32F407VGT6_DISCOVERY_BOARD-PadVDD2)") (class "Default")
      (node (ref "STM32F407VGT6_DISCOVERY_BOARD") (pin "VDD2") (pinfunction "VDD2_VDD2") (pintype "bidirectional"))
    )
    (net (code "136") (name "unconnected-(STM32F407VGT6_DISCOVERY_BOARD-PadVDD3)") (class "Default")
      (node (ref "STM32F407VGT6_DISCOVERY_BOARD") (pin "VDD3") (pinfunction "VDD3_VDD3") (pintype "bidirectional"))
    )
    (net (code "137") (name "unconnected-(TM1-PadE)") (class "Default")
      (node (ref "TM1") (pin "E") (pinfunction "E_E") (pintype "passive"))
    )
    (net (code "138") (name "unconnected-(TM2-PadE)") (class "Default")
      (node (ref "TM2") (pin "E") (pinfunction "E_E") (pintype "passive"))
    )
  )
)
